# ai_breakout_ws2812.net
KiCad netlist of a schematic drawn in EAGLE
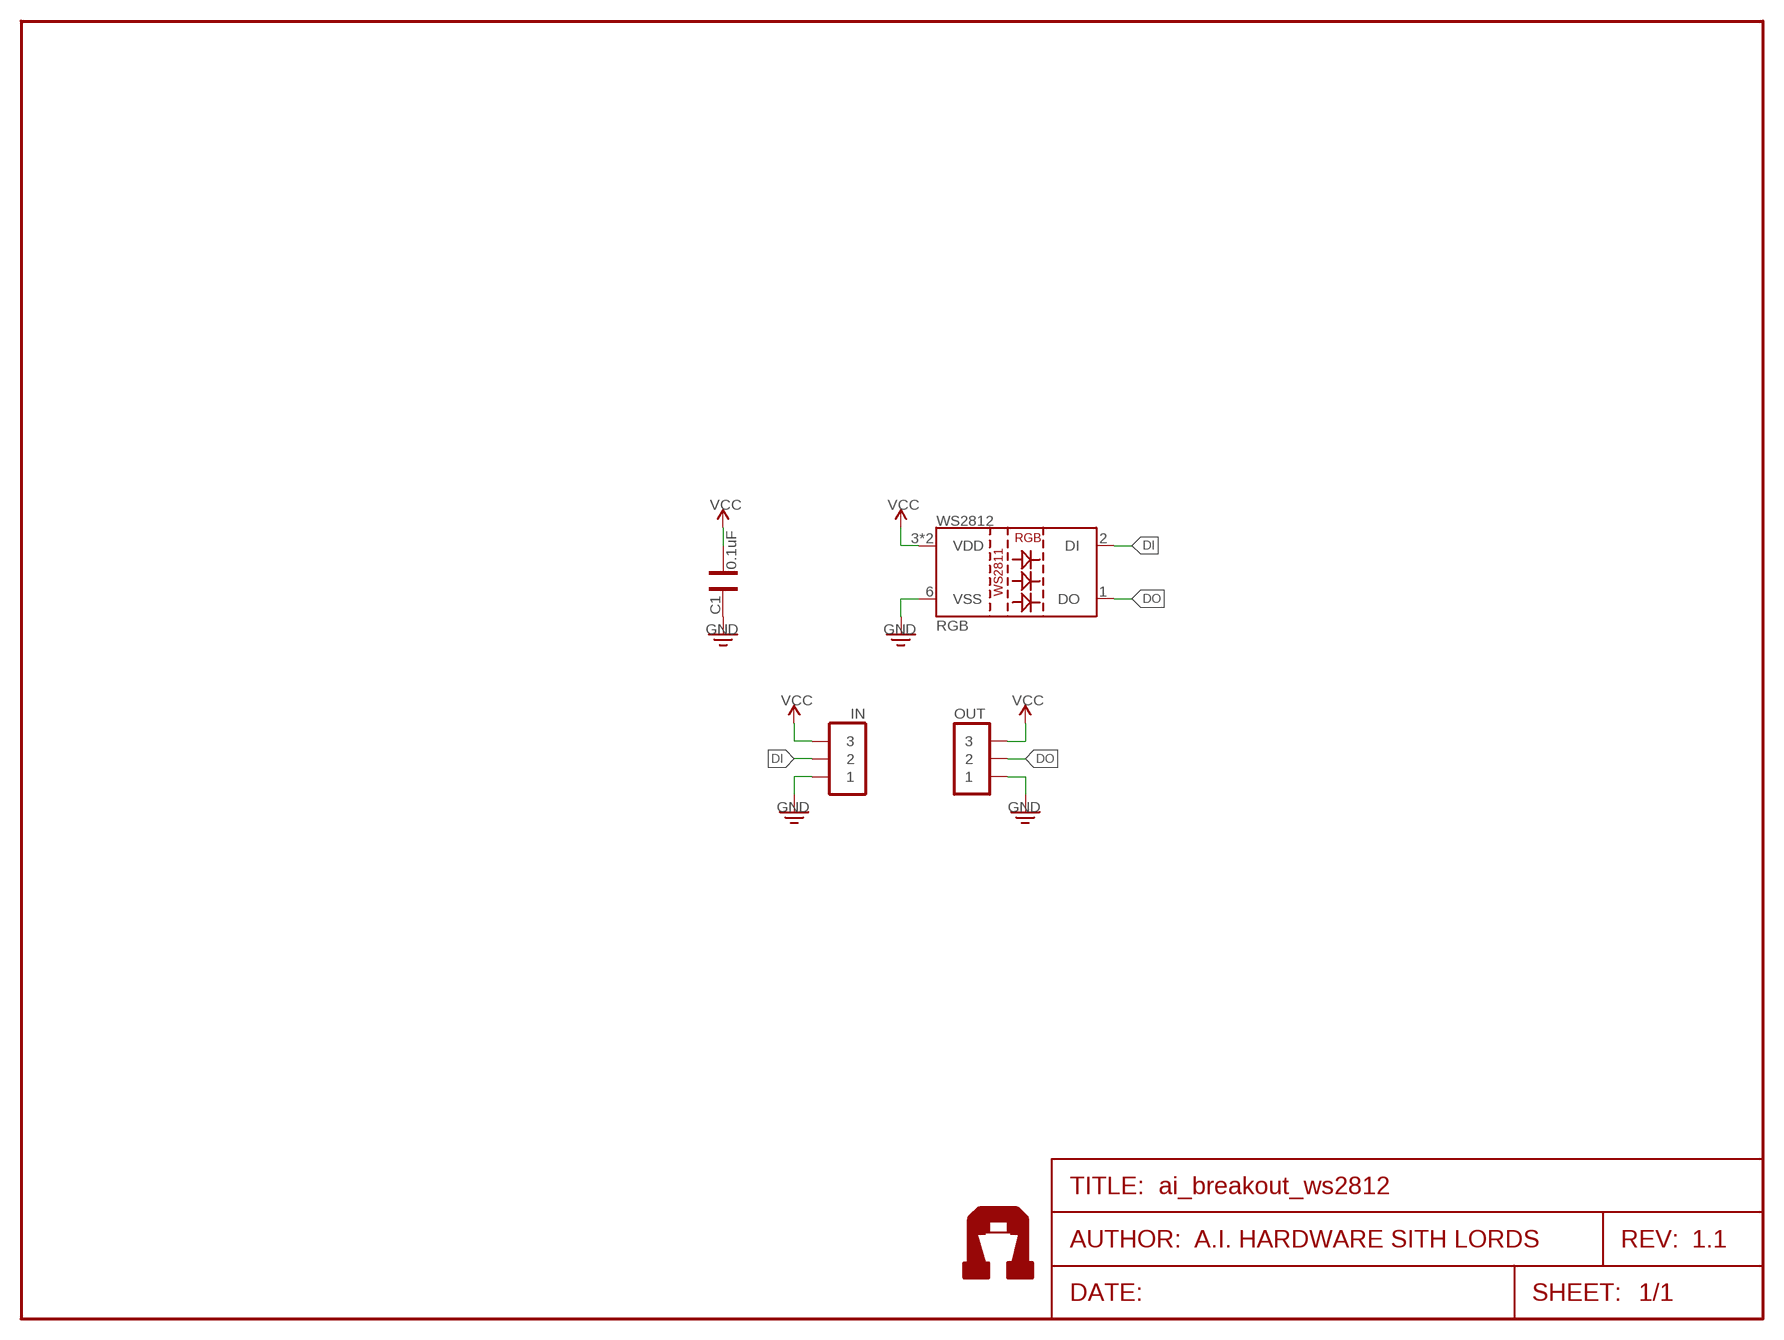
[diagram p0: schematic, sheet 1]

(export (version "E")
  (design (tool "Eeschema 10.0.6"))
  (components
    (comp (ref "C1")
      (value "0.1uF")
      (footprint "eagle-import:CAP-0603")
      (libsource (lib "eagle-import") (part "CAP0603"))
    )
    (comp (ref "IN")
      (value "1X03")
      (footprint "eagle-import:1X03")
      (libsource (lib "eagle-import") (part "1X03"))
    )
    (comp (ref "OUT")
      (value "1X03")
      (footprint "eagle-import:1X03")
      (libsource (lib "eagle-import") (part "1X03"))
    )
    (comp (ref "RGB")
      (value "LED-WS2812")
      (footprint "eagle-import:LED-WS2812")
      (libsource (lib "eagle-import") (part "LED-WS2812"))
    )
    (comp (ref "U$5")
      (value "AI-LOGOL")
      (footprint "eagle-import:AI-LOGO-L")
      (libsource (lib "eagle-import") (part "AI-LOGOL"))
    )
  )
  (nets
    (net (code "1") (name "DI") (class "Default")
      (node (ref "IN") (pin "2") (pinfunction "2_2") (pintype "bidirectional"))
      (node (ref "RGB") (pin "2") (pinfunction "DI_2") (pintype "bidirectional"))
    )
    (net (code "2") (name "DO") (class "Default")
      (node (ref "OUT") (pin "2") (pinfunction "2_2") (pintype "bidirectional"))
      (node (ref "RGB") (pin "1") (pinfunction "DO_1") (pintype "bidirectional"))
    )
    (net (code "3") (name "GND") (class "Default")
      (node (ref "C1") (pin "2") (pinfunction "2_2") (pintype "passive"))
      (node (ref "IN") (pin "1") (pinfunction "1_1") (pintype "bidirectional"))
      (node (ref "OUT") (pin "1") (pinfunction "1_1") (pintype "bidirectional"))
      (node (ref "RGB") (pin "6") (pinfunction "VSS_6") (pintype "bidirectional"))
    )
    (net (code "4") (name "VCC") (class "Default")
      (node (ref "C1") (pin "1") (pinfunction "1_1") (pintype "passive"))
      (node (ref "IN") (pin "3") (pinfunction "3_3") (pintype "bidirectional"))
      (node (ref "OUT") (pin "3") (pinfunction "3_3") (pintype "bidirectional"))
      (node (ref "RGB") (pin "3") (pinfunction "VDD_3") (pintype "bidirectional"))
      (node (ref "RGB") (pin "5") (pinfunction "VDD_5") (pintype "bidirectional"))
    )
  )
)
